# MainBoard.net
KiCad netlist of a schematic drawn in Altium Designer
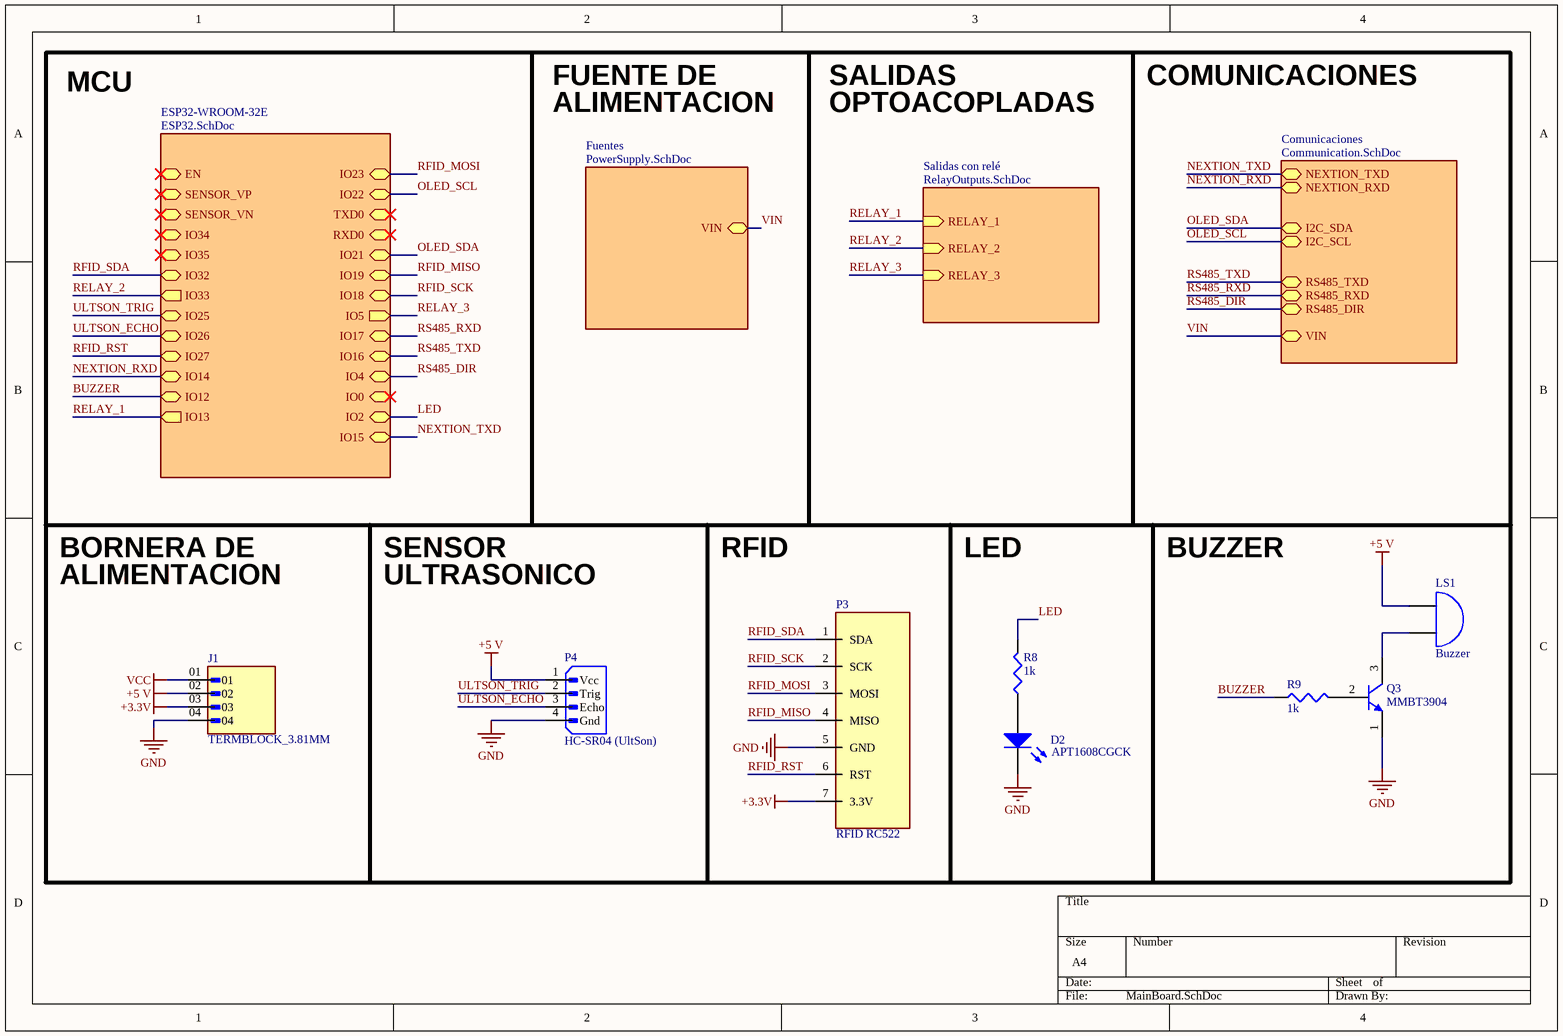
[diagram p0: MainBoard.SchDoc]

(export (version "E")
  (design (tool "Eeschema 10.0.6"))
  (components
    (comp (ref "D2")
      (value "APT1608CGCK")
      (footprint "ChipDiode1608")
      (description "LED 1.6x0.8 mm 570 nm GRN CLR SMD")
      (fields (field (name "PUBLISHER") "Altium Limited"))
      (libsource (lib "Miscellaneous Devices") (part "LED2"))
    )
    (comp (ref "J1")
      (value "TERMBLOCK_3.81MM")
      (footprint "TERMBLOCK_3.81MM_90DEG_4POS")
      (description "TERMBLOCK_3.81MM_90DEG_4POS (DigiKey: 1803293)")
      (libsource (lib "MH_Lib") (part "TERMBLOCK_3.81MM_90DEG_4POS"))
    )
    (comp (ref "LS1")
      (value "Buzzer")
      (footprint "BUZZER")
      (description "Electrical Bell")
      (fields (field (name "PUBLISHER") "Altium Limited"))
      (libsource (lib "Miscellaneous Devices") (part "Bell"))
    )
    (comp (ref "P3")
      (value "RFID RC522")
      (footprint "MOD_RFID_RC522")
      (description "Módulo RFID RC522 con conector B7B-XH-A")
      (libsource (lib "MH_Lib") (part "MOD_RFID_RC522"))
    )
    (comp (ref "P4")
      (value "HC-SR04 (UltSon)")
      (footprint "CONN-B4B-XH-A")
      (description "B4B-XH-A - CONN HEADER VERT 4POS 2.5MM")
      (libsource (lib "MH_Lib") (part "CONN-B4B-XH-A"))
    )
    (comp (ref "Q3")
      (value "MMBT3904")
      (footprint "MMBT3904")
      (description "TRANS NPN 40V 0.2A SOT-23-3")
      (libsource (lib "MH_Lib") (part "MMBT3904"))
    )
    (comp (ref "R8")
      (value "1k")
      (footprint "RESC2012N")
      (description "Resistor")
      (fields (field (name "PUBLISHER") "Altium Limited"))
      (libsource (lib "Miscellaneous Devices") (part "Res3"))
    )
    (comp (ref "R9")
      (value "1k")
      (footprint "RESC2012N")
      (description "Resistor")
      (fields (field (name "PUBLISHER") "Altium Limited"))
      (libsource (lib "Miscellaneous Devices") (part "Res3"))
    )
  )
  (nets
    (net (code "1") (name "+3.3V") (class "Default")
      (node (ref "J1") (pin "03") (pinfunction "03_03") (pintype "passive"))
      (node (ref "P3") (pin "7") (pinfunction "3.3V_7") (pintype "passive"))
    )
    (net (code "2") (name "+5 V") (class "Default")
      (node (ref "J1") (pin "02") (pinfunction "02_02") (pintype "passive"))
      (node (ref "LS1") (pin "1") (pinfunction "A_1") (pintype "passive"))
      (node (ref "P4") (pin "1") (pinfunction "Vcc_1") (pintype "passive"))
    )
    (net (code "3") (name "/BUZZER") (class "Default")
      (node (ref "R9") (pin "1") (pinfunction "1_1") (pintype "passive"))
    )
    (net (code "8") (name "/LED") (class "Default")
      (node (ref "R8") (pin "2") (pinfunction "2_2") (pintype "passive"))
    )
    (net (code "16") (name "/RFID_MISO") (class "Default")
      (node (ref "P3") (pin "4") (pinfunction "MISO_4") (pintype "passive"))
    )
    (net (code "17") (name "/RFID_MOSI") (class "Default")
      (node (ref "P3") (pin "3") (pinfunction "MOSI_3") (pintype "passive"))
    )
    (net (code "18") (name "/RFID_RST") (class "Default")
      (node (ref "P3") (pin "6") (pinfunction "RST_6") (pintype "passive"))
    )
    (net (code "19") (name "/RFID_SCK") (class "Default")
      (node (ref "P3") (pin "2") (pinfunction "SCK_2") (pintype "passive"))
    )
    (net (code "20") (name "/RFID_SDA") (class "Default")
      (node (ref "P3") (pin "1") (pinfunction "SDA_1") (pintype "passive"))
    )
    (net (code "28") (name "/ULTSON_ECHO") (class "Default")
      (node (ref "P4") (pin "3") (pinfunction "Echo_3") (pintype "passive"))
    )
    (net (code "29") (name "/ULTSON_TRIG") (class "Default")
      (node (ref "P4") (pin "2") (pinfunction "Trig_2") (pintype "passive"))
    )
    (net (code "31") (name "GND") (class "Default")
      (node (ref "D2") (pin "2") (pinfunction "K_2") (pintype "passive"))
      (node (ref "J1") (pin "04") (pinfunction "04_04") (pintype "passive"))
      (node (ref "P3") (pin "5") (pinfunction "GND_5") (pintype "passive"))
      (node (ref "P4") (pin "4") (pinfunction "Gnd_4") (pintype "passive"))
      (node (ref "Q3") (pin "1") (pinfunction "E_1") (pintype "passive"))
    )
    (net (code "32") (name "Net-(D2-A)") (class "Default")
      (node (ref "D2") (pin "1") (pinfunction "A_1") (pintype "passive"))
      (node (ref "R8") (pin "1") (pinfunction "1_1") (pintype "passive"))
    )
    (net (code "33") (name "Net-(LS1-B)") (class "Default")
      (node (ref "LS1") (pin "2") (pinfunction "B_2") (pintype "passive"))
      (node (ref "Q3") (pin "3") (pinfunction "C_3") (pintype "passive"))
    )
    (net (code "34") (name "Net-(Q3-B)") (class "Default")
      (node (ref "Q3") (pin "2") (pinfunction "B_2") (pintype "passive"))
      (node (ref "R9") (pin "2") (pinfunction "2_2") (pintype "passive"))
    )
    (net (code "35") (name "VCC") (class "Default")
      (node (ref "J1") (pin "01") (pinfunction "01_01") (pintype "passive"))
    )
  )
)
